# 14_RK3588_VCCIO4.net
KiCad netlist of a schematic drawn in Altium Designer
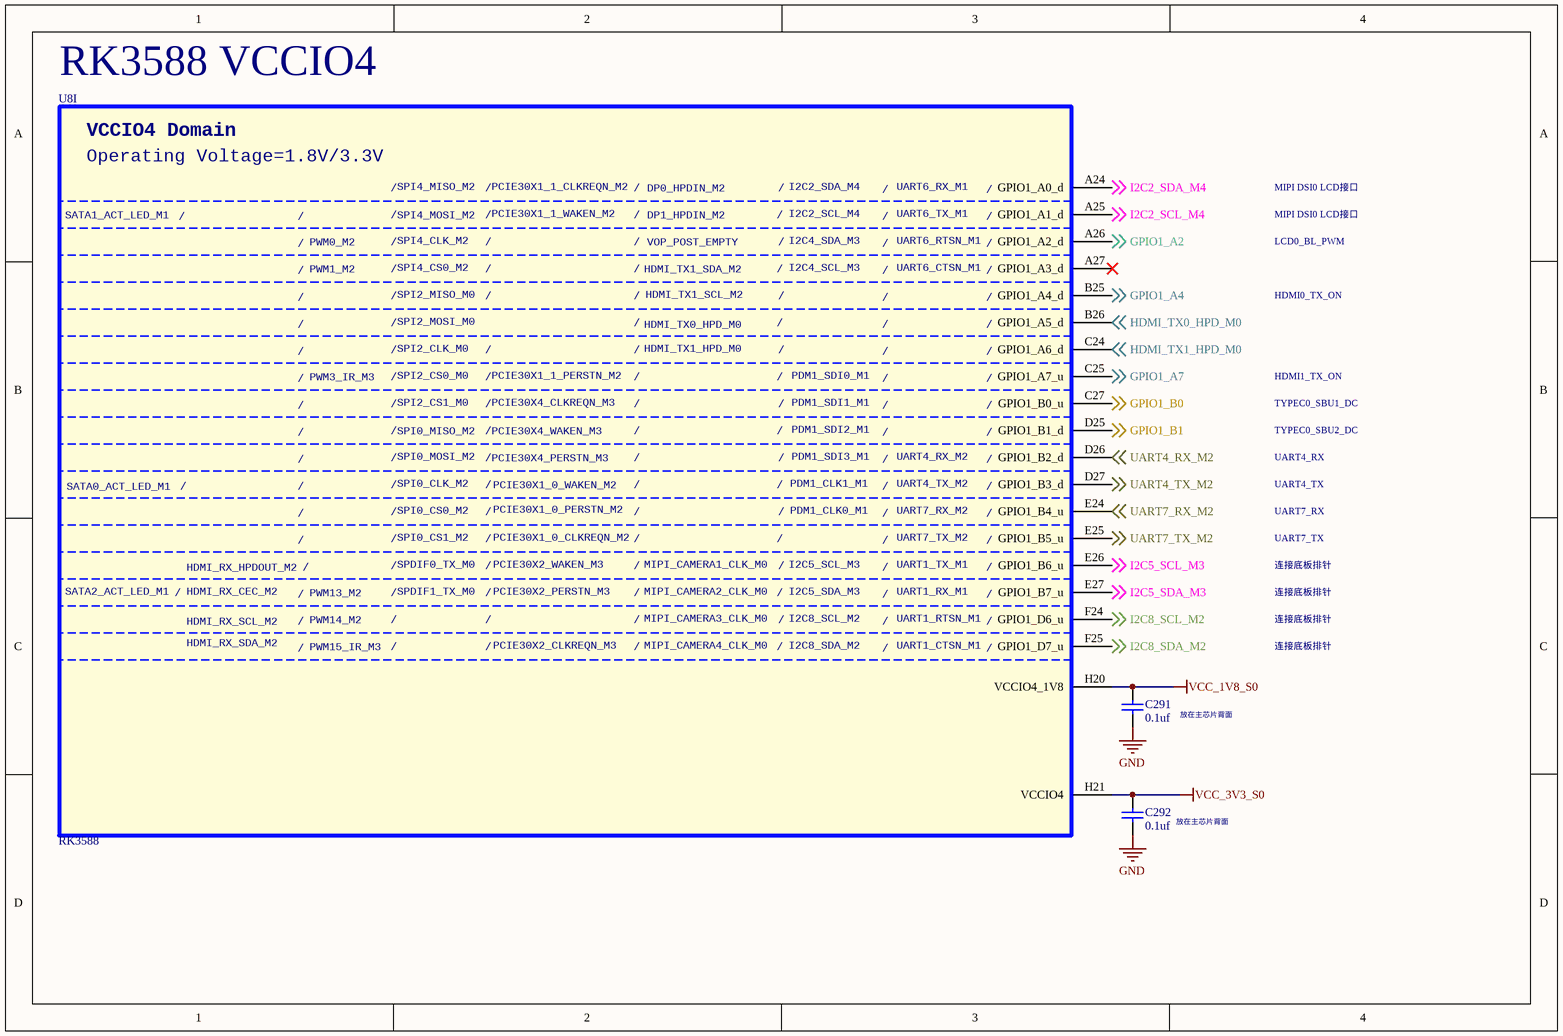
[diagram p0: 14.RK3588_VCCIO4.SchDoc]

(export (version "E")
  (design (tool "Eeschema 10.0.6"))
  (components
    (comp (ref "C291")
      (value "0.1uf")
      (footprint "0.PCB1:C0201_L")
      (description "贴片电容/MLCC电容")
      (libsource (lib "RK3588") (part "C"))
    )
    (comp (ref "C292")
      (value "0.1uf")
      (footprint "0.PCB1:C0201_L")
      (description "贴片电容/MLCC电容")
      (libsource (lib "RK3588") (part "C"))
    )
    (comp (ref "U8")
      (value "RK3588")
      (footprint "0.PCB1:BGA1088_23R00X23R00X2R00")
      (description "ROCKCHIP SOC")
      (libsource (lib "RK3588") (part "SOC_RK3588"))
    )
  )
  (nets
    (net (code "1") (name "GND") (class "Default")
      (node (ref "C291") (pin "1") (pinfunction "1_1") (pintype "passive"))
      (node (ref "C292") (pin "1") (pinfunction "1_1") (pintype "passive"))
    )
    (net (code "2") (name "GPIO1_A2") (class "Default")
      (node (ref "U8") (pin "A26") (pinfunction "GPIO1_A2_d_A26") (pintype "passive"))
    )
    (net (code "3") (name "GPIO1_A4") (class "Default")
      (node (ref "U8") (pin "B25") (pinfunction "GPIO1_A4_d_B25") (pintype "passive"))
    )
    (net (code "4") (name "GPIO1_A7") (class "Default")
      (node (ref "U8") (pin "C25") (pinfunction "GPIO1_A7_u_C25") (pintype "passive"))
    )
    (net (code "5") (name "GPIO1_B0") (class "Default")
      (node (ref "U8") (pin "C27") (pinfunction "GPIO1_B0_u_C27") (pintype "passive"))
    )
    (net (code "6") (name "GPIO1_B1") (class "Default")
      (node (ref "U8") (pin "D25") (pinfunction "GPIO1_B1_d_D25") (pintype "passive"))
    )
    (net (code "7") (name "HDMI_TX0_HPD_M0") (class "Default")
      (node (ref "U8") (pin "B26") (pinfunction "GPIO1_A5_d_B26") (pintype "passive"))
    )
    (net (code "8") (name "HDMI_TX1_HPD_M0") (class "Default")
      (node (ref "U8") (pin "C24") (pinfunction "GPIO1_A6_d_C24") (pintype "passive"))
    )
    (net (code "9") (name "I2C2_SCL_M4") (class "Default")
      (node (ref "U8") (pin "A25") (pinfunction "GPIO1_A1_d_A25") (pintype "passive"))
    )
    (net (code "10") (name "I2C2_SDA_M4") (class "Default")
      (node (ref "U8") (pin "A24") (pinfunction "GPIO1_A0_d_A24") (pintype "passive"))
    )
    (net (code "11") (name "I2C5_SCL_M3") (class "Default")
      (node (ref "U8") (pin "E26") (pinfunction "GPIO1_B6_u_E26") (pintype "passive"))
    )
    (net (code "12") (name "I2C5_SDA_M3") (class "Default")
      (node (ref "U8") (pin "E27") (pinfunction "GPIO1_B7_u_E27") (pintype "passive"))
    )
    (net (code "13") (name "I2C8_SCL_M2") (class "Default")
      (node (ref "U8") (pin "F24") (pinfunction "GPIO1_D6_u_F24") (pintype "passive"))
    )
    (net (code "14") (name "I2C8_SDA_M2") (class "Default")
      (node (ref "U8") (pin "F25") (pinfunction "GPIO1_D7_u_F25") (pintype "passive"))
    )
    (net (code "15") (name "UART4_RX_M2") (class "Default")
      (node (ref "U8") (pin "D26") (pinfunction "GPIO1_B2_d_D26") (pintype "passive"))
    )
    (net (code "16") (name "UART4_TX_M2") (class "Default")
      (node (ref "U8") (pin "D27") (pinfunction "GPIO1_B3_d_D27") (pintype "passive"))
    )
    (net (code "17") (name "UART7_RX_M2") (class "Default")
      (node (ref "U8") (pin "E24") (pinfunction "GPIO1_B4_u_E24") (pintype "passive"))
    )
    (net (code "18") (name "UART7_TX_M2") (class "Default")
      (node (ref "U8") (pin "E25") (pinfunction "GPIO1_B5_u_E25") (pintype "passive"))
    )
    (net (code "19") (name "VCC_1V8_S0") (class "Default")
      (node (ref "C291") (pin "2") (pinfunction "2_2") (pintype "passive"))
      (node (ref "U8") (pin "H20") (pinfunction "VCCIO4_1V8_H20") (pintype "passive"))
    )
    (net (code "20") (name "VCC_3V3_S0") (class "Default")
      (node (ref "C292") (pin "2") (pinfunction "2_2") (pintype "passive"))
      (node (ref "U8") (pin "H21") (pinfunction "VCCIO4_H21") (pintype "passive"))
    )
    (net (code "21") (name "unconnected-(U8I-GPIO1_A3_d-PadA27)") (class "Default")
      (node (ref "U8") (pin "A27") (pinfunction "GPIO1_A3_d_A27") (pintype "passive+no_connect"))
    )
  )
)
